# ServoMicro.net
KiCad netlist of a schematic drawn in EAGLE
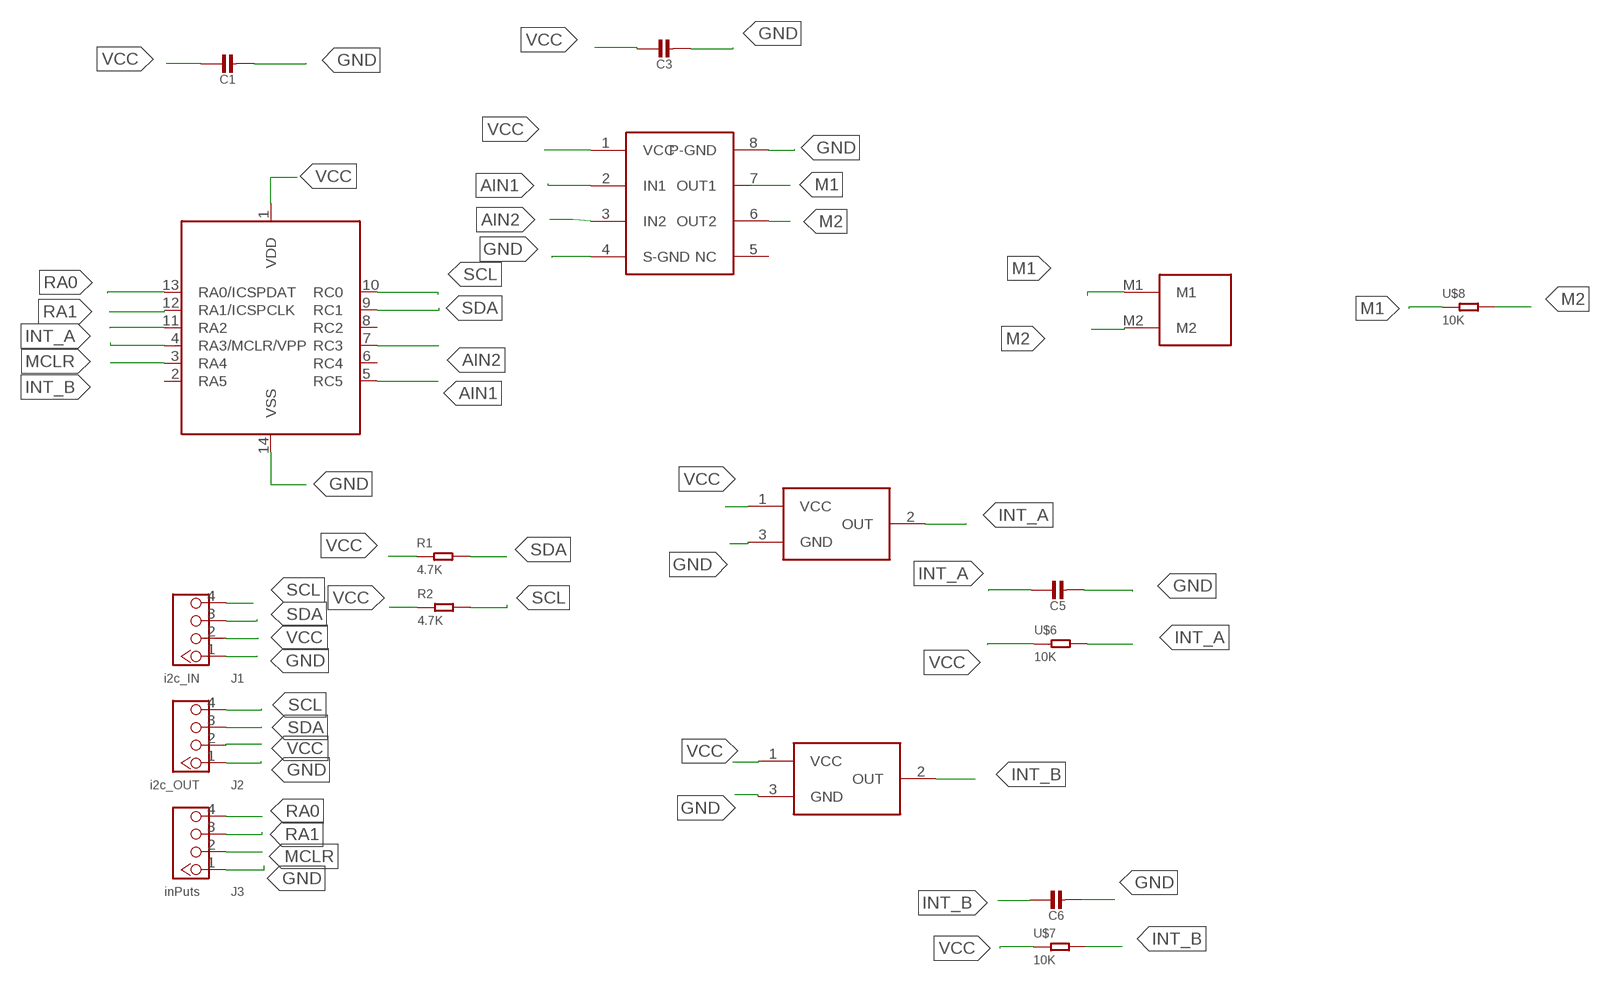
[diagram p0: schematic, sheet 1]

(export (version "E")
  (design (tool "Eeschema 10.0.6"))
  (components
    (comp (ref "C1")
      (value "CAP_CERAMIC0805-NOOUTLINE")
      (footprint "eagle-import:0805-NO")
      (libsource (lib "eagle-import") (part "CAP_CERAMIC0805-NOOUTLINE"))
    )
    (comp (ref "C3")
      (value "CAP_CERAMIC0805-NOOUTLINE")
      (footprint "eagle-import:0805-NO")
      (libsource (lib "eagle-import") (part "CAP_CERAMIC0805-NOOUTLINE"))
    )
    (comp (ref "C5")
      (value "CAP_CERAMIC0805-NOOUTLINE")
      (footprint "eagle-import:0805-NO")
      (libsource (lib "eagle-import") (part "CAP_CERAMIC0805-NOOUTLINE"))
    )
    (comp (ref "C6")
      (value "CAP_CERAMIC0805-NOOUTLINE")
      (footprint "eagle-import:0805-NO")
      (libsource (lib "eagle-import") (part "CAP_CERAMIC0805-NOOUTLINE"))
    )
    (comp (ref "J1")
      (value "i2c_IN")
      (footprint "eagle-import:HW4-2.0")
      (libsource (lib "eagle-import") (part "GROVE-CONNECTOR-DIP(4P-2.0)"))
    )
    (comp (ref "J2")
      (value "i2c_OUT")
      (footprint "eagle-import:HW4-2.0")
      (libsource (lib "eagle-import") (part "GROVE-CONNECTOR-DIP(4P-2.0)"))
    )
    (comp (ref "J3")
      (value "inPuts")
      (footprint "eagle-import:HW4-2.0")
      (libsource (lib "eagle-import") (part "GROVE-CONNECTOR-DIP(4P-2.0)"))
    )
    (comp (ref "R1")
      (value "4.7K")
      (footprint "eagle-import:R0805")
      (fields (field (name "MPN") "RC0805JR-074K7L"))
      (libsource (lib "eagle-import") (part "SMD-RES-4.7K-5%-1/8W(0805)"))
    )
    (comp (ref "R2")
      (value "4.7K")
      (footprint "eagle-import:R0805")
      (fields (field (name "MPN") "RC0805JR-074K7L"))
      (libsource (lib "eagle-import") (part "SMD-RES-4.7K-5%-1/8W(0805)"))
    )
    (comp (ref "U$1")
      (value "LB1938DFA_A")
      (footprint "eagle-import:MSOP8")
      (libsource (lib "eagle-import") (part "LB1938DFA_A"))
    )
    (comp (ref "U$2")
      (value "DRV5021-Q1")
      (footprint "eagle-import:SOT-23")
      (libsource (lib "eagle-import") (part "DRV5021-Q1"))
    )
    (comp (ref "U$3")
      (value "DRV5021-Q1")
      (footprint "eagle-import:SOT-23")
      (libsource (lib "eagle-import") (part "DRV5021-Q1"))
    )
    (comp (ref "U$4")
      (value "MICRO_MOTOR")
      (footprint "eagle-import:MICRO_MOTOR")
      (libsource (lib "eagle-import") (part "MICRO_MOTOR"))
    )
    (comp (ref "U$5")
      (value "PIC16F1503SOIC")
      (footprint "eagle-import:SO-14")
      (libsource (lib "eagle-import") (part "PIC16F1503SOIC"))
    )
    (comp (ref "U$6")
      (value "10K")
      (footprint "eagle-import:R0805")
      (fields (field (name "MPN") "RC0805FR-0710KL"))
      (libsource (lib "eagle-import") (part "SMD-RES-10K-1%-1/8W(0805)"))
    )
    (comp (ref "U$7")
      (value "10K")
      (footprint "eagle-import:R0805")
      (fields (field (name "MPN") "RC0805FR-0710KL"))
      (libsource (lib "eagle-import") (part "SMD-RES-10K-1%-1/8W(0805)"))
    )
    (comp (ref "U$8")
      (value "10K")
      (footprint "eagle-import:R0805")
      (fields (field (name "MPN") "RC0805FR-0710KL"))
      (libsource (lib "eagle-import") (part "SMD-RES-10K-1%-1/8W(0805)"))
    )
  )
  (nets
    (net (code "1") (name "AIN1") (class "Default")
      (node (ref "U$1") (pin "2") (pinfunction "IN1_2") (pintype "input"))
      (node (ref "U$5") (pin "5") (pinfunction "RC5_5") (pintype "bidirectional"))
    )
    (net (code "2") (name "AIN2") (class "Default")
      (node (ref "U$1") (pin "3") (pinfunction "IN2_3") (pintype "input"))
      (node (ref "U$5") (pin "7") (pinfunction "RC3_7") (pintype "bidirectional"))
    )
    (net (code "3") (name "GND") (class "Default")
      (node (ref "C1") (pin "2") (pinfunction "2_2") (pintype "passive"))
      (node (ref "C3") (pin "2") (pinfunction "2_2") (pintype "passive"))
      (node (ref "C5") (pin "2") (pinfunction "2_2") (pintype "passive"))
      (node (ref "C6") (pin "2") (pinfunction "2_2") (pintype "passive"))
      (node (ref "J1") (pin "1") (pinfunction "1_1") (pintype "bidirectional"))
      (node (ref "J2") (pin "1") (pinfunction "1_1") (pintype "bidirectional"))
      (node (ref "J3") (pin "1") (pinfunction "1_1") (pintype "bidirectional"))
      (node (ref "U$1") (pin "4") (pinfunction "S-GND_4") (pintype "power_in"))
      (node (ref "U$1") (pin "8") (pinfunction "P-GND_8") (pintype "power_in"))
      (node (ref "U$2") (pin "3") (pinfunction "GND_3") (pintype "power_in"))
      (node (ref "U$3") (pin "3") (pinfunction "GND_3") (pintype "power_in"))
      (node (ref "U$5") (pin "14") (pinfunction "VSS_14") (pintype "power_in"))
    )
    (net (code "4") (name "INT_A") (class "Default")
      (node (ref "C5") (pin "1") (pinfunction "1_1") (pintype "passive"))
      (node (ref "U$2") (pin "2") (pinfunction "OUT_2") (pintype "output"))
      (node (ref "U$5") (pin "11") (pinfunction "RA2_11") (pintype "bidirectional"))
      (node (ref "U$6") (pin "2") (pinfunction "2_2") (pintype "passive"))
    )
    (net (code "5") (name "INT_B") (class "Default")
      (node (ref "C6") (pin "1") (pinfunction "1_1") (pintype "passive"))
      (node (ref "U$3") (pin "2") (pinfunction "OUT_2") (pintype "output"))
      (node (ref "U$5") (pin "3") (pinfunction "RA4_3") (pintype "bidirectional"))
      (node (ref "U$7") (pin "2") (pinfunction "2_2") (pintype "passive"))
    )
    (net (code "6") (name "M1") (class "Default")
      (node (ref "U$1") (pin "7") (pinfunction "OUT1_7") (pintype "output"))
      (node (ref "U$4") (pin "M1") (pinfunction "M1_M1") (pintype "input"))
      (node (ref "U$8") (pin "1") (pinfunction "1_1") (pintype "passive"))
    )
    (net (code "7") (name "M2") (class "Default")
      (node (ref "U$1") (pin "6") (pinfunction "OUT2_6") (pintype "output"))
      (node (ref "U$4") (pin "M2") (pinfunction "M2_M2") (pintype "input"))
      (node (ref "U$8") (pin "2") (pinfunction "2_2") (pintype "passive"))
    )
    (net (code "8") (name "MCLR") (class "Default")
      (node (ref "J3") (pin "2") (pinfunction "2_2") (pintype "bidirectional"))
      (node (ref "U$5") (pin "4") (pinfunction "RA3/MCLR/VPP_4") (pintype "input"))
    )
    (net (code "9") (name "RA0") (class "Default")
      (node (ref "J3") (pin "4") (pinfunction "4_4") (pintype "bidirectional"))
      (node (ref "U$5") (pin "13") (pinfunction "RA0/ICSPDAT_13") (pintype "bidirectional"))
    )
    (net (code "10") (name "RA1") (class "Default")
      (node (ref "J3") (pin "3") (pinfunction "3_3") (pintype "bidirectional"))
      (node (ref "U$5") (pin "12") (pinfunction "RA1/ICSPCLK_12") (pintype "bidirectional"))
    )
    (net (code "11") (name "SCL") (class "Default")
      (node (ref "J1") (pin "4") (pinfunction "4_4") (pintype "bidirectional"))
      (node (ref "J2") (pin "4") (pinfunction "4_4") (pintype "bidirectional"))
      (node (ref "R2") (pin "2") (pinfunction "2_2") (pintype "passive"))
      (node (ref "U$5") (pin "10") (pinfunction "RC0_10") (pintype "bidirectional"))
    )
    (net (code "12") (name "SDA") (class "Default")
      (node (ref "J1") (pin "3") (pinfunction "3_3") (pintype "bidirectional"))
      (node (ref "J2") (pin "3") (pinfunction "3_3") (pintype "bidirectional"))
      (node (ref "R1") (pin "2") (pinfunction "2_2") (pintype "passive"))
      (node (ref "U$5") (pin "9") (pinfunction "RC1_9") (pintype "bidirectional"))
    )
    (net (code "13") (name "VCC") (class "Default")
      (node (ref "C1") (pin "1") (pinfunction "1_1") (pintype "passive"))
      (node (ref "C3") (pin "1") (pinfunction "1_1") (pintype "passive"))
      (node (ref "J1") (pin "2") (pinfunction "2_2") (pintype "bidirectional"))
      (node (ref "J2") (pin "2") (pinfunction "2_2") (pintype "bidirectional"))
      (node (ref "R1") (pin "1") (pinfunction "1_1") (pintype "passive"))
      (node (ref "R2") (pin "1") (pinfunction "1_1") (pintype "passive"))
      (node (ref "U$1") (pin "1") (pinfunction "VCC_1") (pintype "power_in"))
      (node (ref "U$2") (pin "1") (pinfunction "VCC_1") (pintype "power_in"))
      (node (ref "U$3") (pin "1") (pinfunction "VCC_1") (pintype "power_in"))
      (node (ref "U$5") (pin "1") (pinfunction "VDD_1") (pintype "power_in"))
      (node (ref "U$6") (pin "1") (pinfunction "1_1") (pintype "passive"))
      (node (ref "U$7") (pin "1") (pinfunction "1_1") (pintype "passive"))
    )
    (net (code "14") (name "unconnected-(U$1-NC-Pad5)") (class "Default")
      (node (ref "U$1") (pin "5") (pinfunction "NC_5") (pintype "no_connect"))
    )
    (net (code "15") (name "unconnected-(U$5-RA5-Pad2)") (class "Default")
      (node (ref "U$5") (pin "2") (pinfunction "RA5_2") (pintype "bidirectional"))
    )
    (net (code "16") (name "unconnected-(U$5-RC2-Pad8)") (class "Default")
      (node (ref "U$5") (pin "8") (pinfunction "RC2_8") (pintype "bidirectional"))
    )
    (net (code "17") (name "unconnected-(U$5-RC4-Pad6)") (class "Default")
      (node (ref "U$5") (pin "6") (pinfunction "RC4_6") (pintype "bidirectional"))
    )
  )
)
